# do.net
KiCad netlist of a schematic drawn in Altium Designer
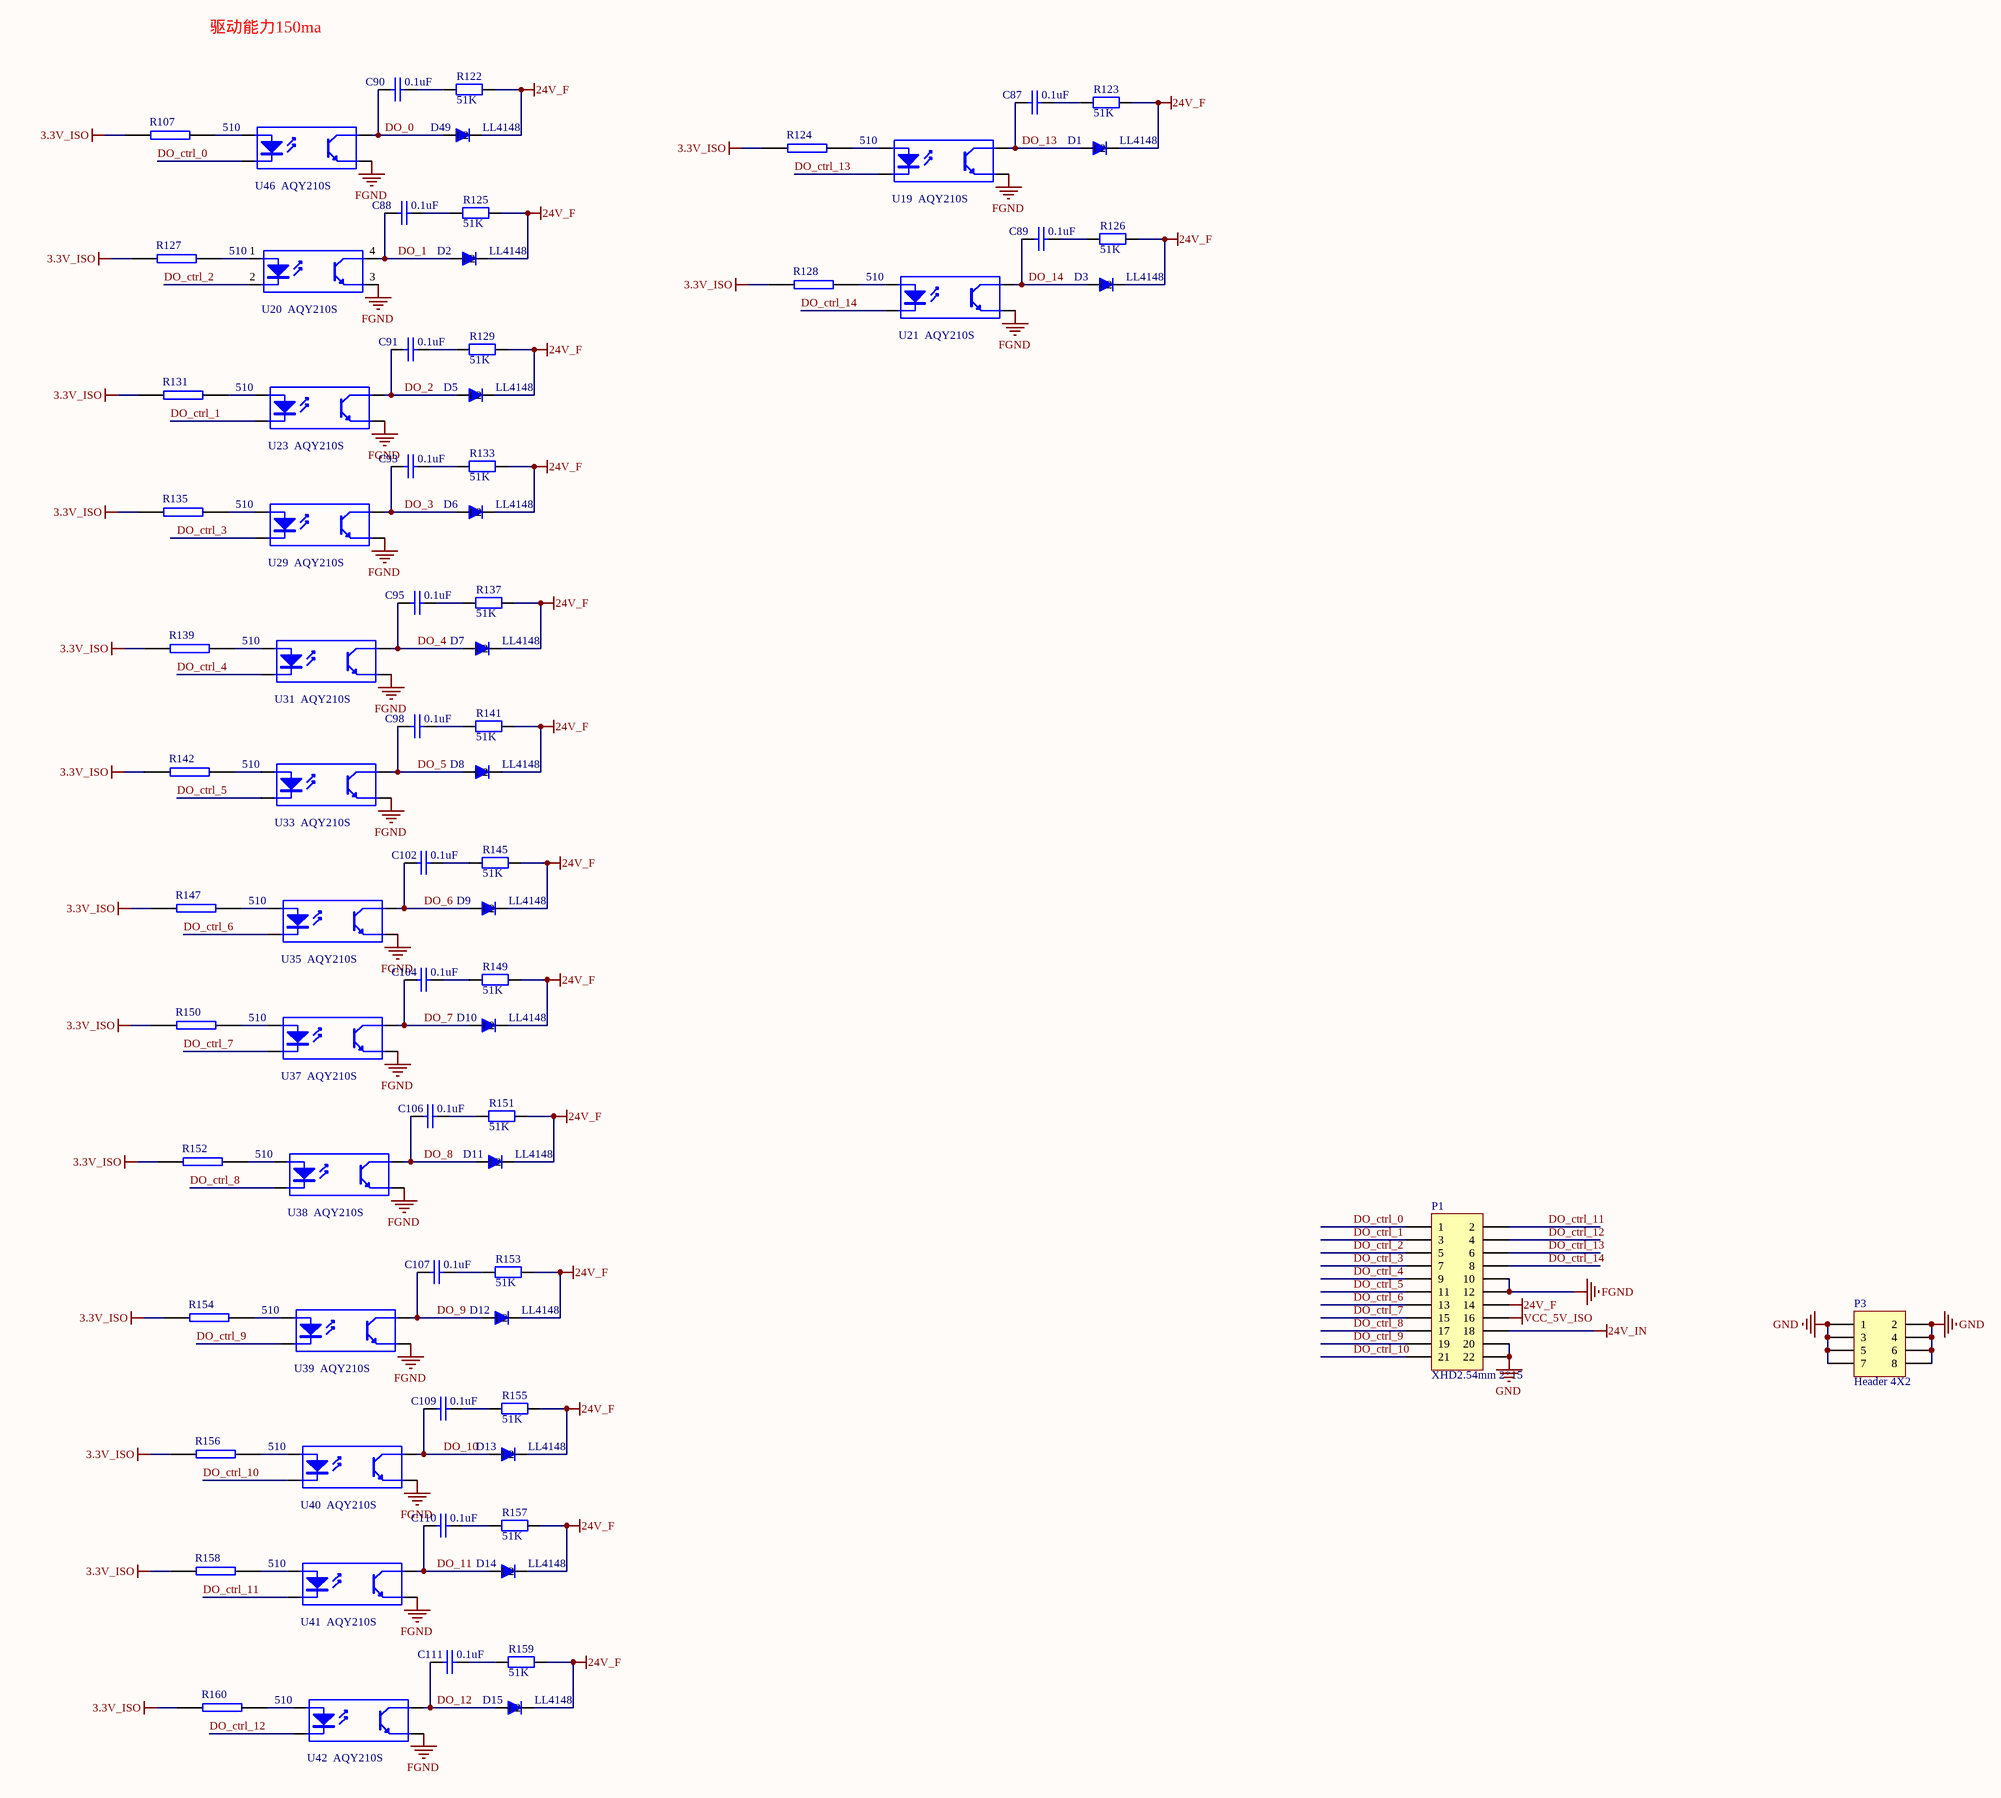
[diagram p0: do.SchDoc]

(export (version "E")
  (design (tool "Eeschema 10.0.6"))
  (components
    (comp (ref "C87")
      (value "0.1uF")
      (footprint "0603C")
      (description "Capacitor")
      (libsource (lib "*") (part "CAP"))
    )
    (comp (ref "C88")
      (value "0.1uF")
      (footprint "0603C")
      (description "Capacitor")
      (libsource (lib "*") (part "CAP"))
    )
    (comp (ref "C89")
      (value "0.1uF")
      (footprint "0603C")
      (description "Capacitor")
      (libsource (lib "*") (part "CAP"))
    )
    (comp (ref "C90")
      (value "0.1uF")
      (footprint "0603C")
      (description "Capacitor")
      (libsource (lib "*") (part "CAP"))
    )
    (comp (ref "C91")
      (value "0.1uF")
      (footprint "0603C")
      (description "Capacitor")
      (libsource (lib "*") (part "CAP"))
    )
    (comp (ref "C93")
      (value "0.1uF")
      (footprint "0603C")
      (description "Capacitor")
      (libsource (lib "*") (part "CAP"))
    )
    (comp (ref "C95")
      (value "0.1uF")
      (footprint "0603C")
      (description "Capacitor")
      (libsource (lib "*") (part "CAP"))
    )
    (comp (ref "C98")
      (value "0.1uF")
      (footprint "0603C")
      (description "Capacitor")
      (libsource (lib "*") (part "CAP"))
    )
    (comp (ref "C102")
      (value "0.1uF")
      (footprint "0603C")
      (description "Capacitor")
      (libsource (lib "*") (part "CAP"))
    )
    (comp (ref "C104")
      (value "0.1uF")
      (footprint "0603C")
      (description "Capacitor")
      (libsource (lib "*") (part "CAP"))
    )
    (comp (ref "C106")
      (value "0.1uF")
      (footprint "0603C")
      (description "Capacitor")
      (libsource (lib "*") (part "CAP"))
    )
    (comp (ref "C107")
      (value "0.1uF")
      (footprint "0603C")
      (description "Capacitor")
      (libsource (lib "*") (part "CAP"))
    )
    (comp (ref "C109")
      (value "0.1uF")
      (footprint "0603C")
      (description "Capacitor")
      (libsource (lib "*") (part "CAP"))
    )
    (comp (ref "C110")
      (value "0.1uF")
      (footprint "0603C")
      (description "Capacitor")
      (libsource (lib "*") (part "CAP"))
    )
    (comp (ref "C111")
      (value "0.1uF")
      (footprint "0603C")
      (description "Capacitor")
      (libsource (lib "*") (part "CAP"))
    )
    (comp (ref "D1")
      (value "LL4148")
      (footprint "DO-213AB/LL34/MiniMELF")
      (description "VISHAY,LL4148,圆柱体MiniMELF100V/2A,ROHS")
      (libsource (lib "Device2018") (part "LL4148"))
    )
    (comp (ref "D2")
      (value "LL4148")
      (footprint "DO-213AB/LL34/MiniMELF")
      (description "VISHAY,LL4148,圆柱体MiniMELF100V/2A,ROHS")
      (libsource (lib "Device2018") (part "LL4148"))
    )
    (comp (ref "D3")
      (value "LL4148")
      (footprint "DO-213AB/LL34/MiniMELF")
      (description "VISHAY,LL4148,圆柱体MiniMELF100V/2A,ROHS")
      (libsource (lib "Device2018") (part "LL4148"))
    )
    (comp (ref "D5")
      (value "LL4148")
      (footprint "DO-213AB/LL34/MiniMELF")
      (description "VISHAY,LL4148,圆柱体MiniMELF100V/2A,ROHS")
      (libsource (lib "Device2018") (part "LL4148"))
    )
    (comp (ref "D6")
      (value "LL4148")
      (footprint "DO-213AB/LL34/MiniMELF")
      (description "VISHAY,LL4148,圆柱体MiniMELF100V/2A,ROHS")
      (libsource (lib "Device2018") (part "LL4148"))
    )
    (comp (ref "D7")
      (value "LL4148")
      (footprint "DO-213AB/LL34/MiniMELF")
      (description "VISHAY,LL4148,圆柱体MiniMELF100V/2A,ROHS")
      (libsource (lib "Device2018") (part "LL4148"))
    )
    (comp (ref "D8")
      (value "LL4148")
      (footprint "DO-213AB/LL34/MiniMELF")
      (description "VISHAY,LL4148,圆柱体MiniMELF100V/2A,ROHS")
      (libsource (lib "Device2018") (part "LL4148"))
    )
    (comp (ref "D9")
      (value "LL4148")
      (footprint "DO-213AB/LL34/MiniMELF")
      (description "VISHAY,LL4148,圆柱体MiniMELF100V/2A,ROHS")
      (libsource (lib "Device2018") (part "LL4148"))
    )
    (comp (ref "D10")
      (value "LL4148")
      (footprint "DO-213AB/LL34/MiniMELF")
      (description "VISHAY,LL4148,圆柱体MiniMELF100V/2A,ROHS")
      (libsource (lib "Device2018") (part "LL4148"))
    )
    (comp (ref "D11")
      (value "LL4148")
      (footprint "DO-213AB/LL34/MiniMELF")
      (description "VISHAY,LL4148,圆柱体MiniMELF100V/2A,ROHS")
      (libsource (lib "Device2018") (part "LL4148"))
    )
    (comp (ref "D12")
      (value "LL4148")
      (footprint "DO-213AB/LL34/MiniMELF")
      (description "VISHAY,LL4148,圆柱体MiniMELF100V/2A,ROHS")
      (libsource (lib "Device2018") (part "LL4148"))
    )
    (comp (ref "D13")
      (value "LL4148")
      (footprint "DO-213AB/LL34/MiniMELF")
      (description "VISHAY,LL4148,圆柱体MiniMELF100V/2A,ROHS")
      (libsource (lib "Device2018") (part "LL4148"))
    )
    (comp (ref "D14")
      (value "LL4148")
      (footprint "DO-213AB/LL34/MiniMELF")
      (description "VISHAY,LL4148,圆柱体MiniMELF100V/2A,ROHS")
      (libsource (lib "Device2018") (part "LL4148"))
    )
    (comp (ref "D15")
      (value "LL4148")
      (footprint "DO-213AB/LL34/MiniMELF")
      (description "VISHAY,LL4148,圆柱体MiniMELF100V/2A,ROHS")
      (libsource (lib "Device2018") (part "LL4148"))
    )
    (comp (ref "D49")
      (value "LL4148")
      (footprint "DO-213AB/LL34/MiniMELF")
      (description "VISHAY,LL4148,圆柱体MiniMELF100V/2A,ROHS")
      (libsource (lib "Device2018") (part "LL4148"))
    )
    (comp (ref "P1")
      (value "XHD2.54mm 2*15")
      (footprint "HDR2X11")
      (description "Header, 11-Pin, Dual row")
      (fields (field (name "PUBLISHER") "Altium Limited"))
      (libsource (lib "Miscellaneous Connectors") (part "Header 11X2"))
    )
    (comp (ref "P3")
      (value "Header 4X2")
      (footprint "HDR2X4")
      (description "Header, 4-Pin, Dual row")
      (fields (field (name "PUBLISHER") "Altium Limited"))
      (libsource (lib "Miscellaneous Connectors") (part "Header 4X2"))
    )
    (comp (ref "R107") (value "510") (footprint "0603R") (libsource (lib "*") (part "RES2")))
    (comp (ref "R122") (value "51K") (footprint "0603R") (libsource (lib "MQlibrary") (part "Res0805M")))
    (comp (ref "R123") (value "51K") (footprint "0603R") (libsource (lib "MQlibrary") (part "Res0805M")))
    (comp (ref "R124") (value "510") (footprint "0603R") (libsource (lib "*") (part "RES2")))
    (comp (ref "R125") (value "51K") (footprint "0603R") (libsource (lib "MQlibrary") (part "Res0805M")))
    (comp (ref "R126") (value "51K") (footprint "0603R") (libsource (lib "MQlibrary") (part "Res0805M")))
    (comp (ref "R127") (value "510") (footprint "0603R") (libsource (lib "*") (part "RES2")))
    (comp (ref "R128") (value "510") (footprint "0603R") (libsource (lib "*") (part "RES2")))
    (comp (ref "R129") (value "51K") (footprint "0603R") (libsource (lib "MQlibrary") (part "Res0805M")))
    (comp (ref "R131") (value "510") (footprint "0603R") (libsource (lib "*") (part "RES2")))
    (comp (ref "R133") (value "51K") (footprint "0603R") (libsource (lib "MQlibrary") (part "Res0805M")))
    (comp (ref "R135") (value "510") (footprint "0603R") (libsource (lib "*") (part "RES2")))
    (comp (ref "R137") (value "51K") (footprint "0603R") (libsource (lib "MQlibrary") (part "Res0805M")))
    (comp (ref "R139") (value "510") (footprint "0603R") (libsource (lib "*") (part "RES2")))
    (comp (ref "R141") (value "51K") (footprint "0603R") (libsource (lib "MQlibrary") (part "Res0805M")))
    (comp (ref "R142") (value "510") (footprint "0603R") (libsource (lib "*") (part "RES2")))
    (comp (ref "R145") (value "51K") (footprint "0603R") (libsource (lib "MQlibrary") (part "Res0805M")))
    (comp (ref "R147") (value "510") (footprint "0603R") (libsource (lib "*") (part "RES2")))
    (comp (ref "R149") (value "51K") (footprint "0603R") (libsource (lib "MQlibrary") (part "Res0805M")))
    (comp (ref "R150") (value "510") (footprint "0603R") (libsource (lib "*") (part "RES2")))
    (comp (ref "R151") (value "51K") (footprint "0603R") (libsource (lib "MQlibrary") (part "Res0805M")))
    (comp (ref "R152") (value "510") (footprint "0603R") (libsource (lib "*") (part "RES2")))
    (comp (ref "R153") (value "51K") (footprint "0603R") (libsource (lib "MQlibrary") (part "Res0805M")))
    (comp (ref "R154") (value "510") (footprint "0603R") (libsource (lib "*") (part "RES2")))
    (comp (ref "R155") (value "51K") (footprint "0603R") (libsource (lib "MQlibrary") (part "Res0805M")))
    (comp (ref "R156") (value "510") (footprint "0603R") (libsource (lib "*") (part "RES2")))
    (comp (ref "R157") (value "51K") (footprint "0603R") (libsource (lib "MQlibrary") (part "Res0805M")))
    (comp (ref "R158") (value "510") (footprint "0603R") (libsource (lib "*") (part "RES2")))
    (comp (ref "R159") (value "51K") (footprint "0603R") (libsource (lib "MQlibrary") (part "Res0805M")))
    (comp (ref "R160") (value "510") (footprint "0603R") (libsource (lib "*") (part "RES2")))
    (comp (ref "U19")
      (value "AQY210S")
      (footprint "sop4")
      (description "4-Pin Phototransistor Optocoupler")
      (fields (field (name "PUBLISHER") "Altium Limited"))
      (libsource (lib "Miscellaneous Devices") (part "Optoisolator1"))
    )
    (comp (ref "U20")
      (value "AQY210S")
      (footprint "sop4")
      (description "4-Pin Phototransistor Optocoupler")
      (fields (field (name "PUBLISHER") "Altium Limited"))
      (libsource (lib "") (part "Optoisolator1_1"))
    )
    (comp (ref "U21")
      (value "AQY210S")
      (footprint "sop4")
      (description "4-Pin Phototransistor Optocoupler")
      (fields (field (name "PUBLISHER") "Altium Limited"))
      (libsource (lib "Miscellaneous Devices") (part "Optoisolator1"))
    )
    (comp (ref "U23")
      (value "AQY210S")
      (footprint "sop4")
      (description "4-Pin Phototransistor Optocoupler")
      (fields (field (name "PUBLISHER") "Altium Limited"))
      (libsource (lib "Miscellaneous Devices") (part "Optoisolator1"))
    )
    (comp (ref "U29")
      (value "AQY210S")
      (footprint "sop4")
      (description "4-Pin Phototransistor Optocoupler")
      (fields (field (name "PUBLISHER") "Altium Limited"))
      (libsource (lib "Miscellaneous Devices") (part "Optoisolator1"))
    )
    (comp (ref "U31")
      (value "AQY210S")
      (footprint "sop4")
      (description "4-Pin Phototransistor Optocoupler")
      (fields (field (name "PUBLISHER") "Altium Limited"))
      (libsource (lib "Miscellaneous Devices") (part "Optoisolator1"))
    )
    (comp (ref "U33")
      (value "AQY210S")
      (footprint "sop4")
      (description "4-Pin Phototransistor Optocoupler")
      (fields (field (name "PUBLISHER") "Altium Limited"))
      (libsource (lib "Miscellaneous Devices") (part "Optoisolator1"))
    )
    (comp (ref "U35")
      (value "AQY210S")
      (footprint "sop4")
      (description "4-Pin Phototransistor Optocoupler")
      (fields (field (name "PUBLISHER") "Altium Limited"))
      (libsource (lib "Miscellaneous Devices") (part "Optoisolator1"))
    )
    (comp (ref "U37")
      (value "AQY210S")
      (footprint "sop4")
      (description "4-Pin Phototransistor Optocoupler")
      (fields (field (name "PUBLISHER") "Altium Limited"))
      (libsource (lib "Miscellaneous Devices") (part "Optoisolator1"))
    )
    (comp (ref "U38")
      (value "AQY210S")
      (footprint "sop4")
      (description "4-Pin Phototransistor Optocoupler")
      (fields (field (name "PUBLISHER") "Altium Limited"))
      (libsource (lib "Miscellaneous Devices") (part "Optoisolator1"))
    )
    (comp (ref "U39")
      (value "AQY210S")
      (footprint "sop4")
      (description "4-Pin Phototransistor Optocoupler")
      (fields (field (name "PUBLISHER") "Altium Limited"))
      (libsource (lib "Miscellaneous Devices") (part "Optoisolator1"))
    )
    (comp (ref "U40")
      (value "AQY210S")
      (footprint "sop4")
      (description "4-Pin Phototransistor Optocoupler")
      (fields (field (name "PUBLISHER") "Altium Limited"))
      (libsource (lib "Miscellaneous Devices") (part "Optoisolator1"))
    )
    (comp (ref "U41")
      (value "AQY210S")
      (footprint "sop4")
      (description "4-Pin Phototransistor Optocoupler")
      (fields (field (name "PUBLISHER") "Altium Limited"))
      (libsource (lib "Miscellaneous Devices") (part "Optoisolator1"))
    )
    (comp (ref "U42")
      (value "AQY210S")
      (footprint "sop4")
      (description "4-Pin Phototransistor Optocoupler")
      (fields (field (name "PUBLISHER") "Altium Limited"))
      (libsource (lib "Miscellaneous Devices") (part "Optoisolator1"))
    )
    (comp (ref "U46")
      (value "AQY210S")
      (footprint "sop4")
      (description "4-Pin Phototransistor Optocoupler")
      (fields (field (name "PUBLISHER") "Altium Limited"))
      (libsource (lib "Miscellaneous Devices") (part "Optoisolator1"))
    )
  )
  (nets
    (net (code "1") (name "/DO_0") (class "Default")
      (node (ref "C90") (pin "1") (pinfunction "1_1") (pintype "passive"))
      (node (ref "D49") (pin "1") (pinfunction "2_1") (pintype "passive"))
      (node (ref "U46") (pin "4") (pinfunction "C_4") (pintype "passive"))
    )
    (net (code "2") (name "/DO_1") (class "Default")
      (node (ref "C88") (pin "1") (pinfunction "1_1") (pintype "passive"))
      (node (ref "D2") (pin "1") (pinfunction "2_1") (pintype "passive"))
      (node (ref "U20") (pin "4") (pinfunction "C_4") (pintype "passive"))
    )
    (net (code "3") (name "/DO_2") (class "Default")
      (node (ref "C91") (pin "1") (pinfunction "1_1") (pintype "passive"))
      (node (ref "D5") (pin "1") (pinfunction "2_1") (pintype "passive"))
      (node (ref "U23") (pin "4") (pinfunction "C_4") (pintype "passive"))
    )
    (net (code "4") (name "/DO_3") (class "Default")
      (node (ref "C93") (pin "1") (pinfunction "1_1") (pintype "passive"))
      (node (ref "D6") (pin "1") (pinfunction "2_1") (pintype "passive"))
      (node (ref "U29") (pin "4") (pinfunction "C_4") (pintype "passive"))
    )
    (net (code "5") (name "/DO_4") (class "Default")
      (node (ref "C95") (pin "1") (pinfunction "1_1") (pintype "passive"))
      (node (ref "D7") (pin "1") (pinfunction "2_1") (pintype "passive"))
      (node (ref "U31") (pin "4") (pinfunction "C_4") (pintype "passive"))
    )
    (net (code "6") (name "/DO_5") (class "Default")
      (node (ref "C98") (pin "1") (pinfunction "1_1") (pintype "passive"))
      (node (ref "D8") (pin "1") (pinfunction "2_1") (pintype "passive"))
      (node (ref "U33") (pin "4") (pinfunction "C_4") (pintype "passive"))
    )
    (net (code "7") (name "/DO_6") (class "Default")
      (node (ref "C102") (pin "1") (pinfunction "1_1") (pintype "passive"))
      (node (ref "D9") (pin "1") (pinfunction "2_1") (pintype "passive"))
      (node (ref "U35") (pin "4") (pinfunction "C_4") (pintype "passive"))
    )
    (net (code "8") (name "/DO_7") (class "Default")
      (node (ref "C104") (pin "1") (pinfunction "1_1") (pintype "passive"))
      (node (ref "D10") (pin "1") (pinfunction "2_1") (pintype "passive"))
      (node (ref "U37") (pin "4") (pinfunction "C_4") (pintype "passive"))
    )
    (net (code "9") (name "/DO_8") (class "Default")
      (node (ref "C106") (pin "1") (pinfunction "1_1") (pintype "passive"))
      (node (ref "D11") (pin "1") (pinfunction "2_1") (pintype "passive"))
      (node (ref "U38") (pin "4") (pinfunction "C_4") (pintype "passive"))
    )
    (net (code "10") (name "/DO_9") (class "Default")
      (node (ref "C107") (pin "1") (pinfunction "1_1") (pintype "passive"))
      (node (ref "D12") (pin "1") (pinfunction "2_1") (pintype "passive"))
      (node (ref "U39") (pin "4") (pinfunction "C_4") (pintype "passive"))
    )
    (net (code "11") (name "/DO_10") (class "Default")
      (node (ref "C109") (pin "1") (pinfunction "1_1") (pintype "passive"))
      (node (ref "D13") (pin "1") (pinfunction "2_1") (pintype "passive"))
      (node (ref "U40") (pin "4") (pinfunction "C_4") (pintype "passive"))
    )
    (net (code "12") (name "/DO_11") (class "Default")
      (node (ref "C110") (pin "1") (pinfunction "1_1") (pintype "passive"))
      (node (ref "D14") (pin "1") (pinfunction "2_1") (pintype "passive"))
      (node (ref "U41") (pin "4") (pinfunction "C_4") (pintype "passive"))
    )
    (net (code "13") (name "/DO_12") (class "Default")
      (node (ref "C111") (pin "1") (pinfunction "1_1") (pintype "passive"))
      (node (ref "D15") (pin "1") (pinfunction "2_1") (pintype "passive"))
      (node (ref "U42") (pin "4") (pinfunction "C_4") (pintype "passive"))
    )
    (net (code "14") (name "/DO_13") (class "Default")
      (node (ref "C87") (pin "1") (pinfunction "1_1") (pintype "passive"))
      (node (ref "D1") (pin "1") (pinfunction "2_1") (pintype "passive"))
      (node (ref "U19") (pin "4") (pinfunction "C_4") (pintype "passive"))
    )
    (net (code "15") (name "/DO_14") (class "Default")
      (node (ref "C89") (pin "1") (pinfunction "1_1") (pintype "passive"))
      (node (ref "D3") (pin "1") (pinfunction "2_1") (pintype "passive"))
      (node (ref "U21") (pin "4") (pinfunction "C_4") (pintype "passive"))
    )
    (net (code "16") (name "/DO_ctrl_0") (class "Default")
      (node (ref "P1") (pin "1") (pinfunction "1_1") (pintype "passive"))
      (node (ref "U46") (pin "2") (pinfunction "K_2") (pintype "passive"))
    )
    (net (code "17") (name "/DO_ctrl_1") (class "Default")
      (node (ref "P1") (pin "3") (pinfunction "3_3") (pintype "passive"))
      (node (ref "U23") (pin "2") (pinfunction "K_2") (pintype "passive"))
    )
    (net (code "18") (name "/DO_ctrl_2") (class "Default")
      (node (ref "P1") (pin "5") (pinfunction "5_5") (pintype "passive"))
      (node (ref "U20") (pin "2") (pinfunction "K_2") (pintype "passive"))
    )
    (net (code "19") (name "/DO_ctrl_3") (class "Default")
      (node (ref "P1") (pin "7") (pinfunction "7_7") (pintype "passive"))
      (node (ref "U29") (pin "2") (pinfunction "K_2") (pintype "passive"))
    )
    (net (code "20") (name "/DO_ctrl_4") (class "Default")
      (node (ref "P1") (pin "9") (pinfunction "9_9") (pintype "passive"))
      (node (ref "U31") (pin "2") (pinfunction "K_2") (pintype "passive"))
    )
    (net (code "21") (name "/DO_ctrl_5") (class "Default")
      (node (ref "P1") (pin "11") (pinfunction "11_11") (pintype "passive"))
      (node (ref "U33") (pin "2") (pinfunction "K_2") (pintype "passive"))
    )
    (net (code "22") (name "/DO_ctrl_6") (class "Default")
      (node (ref "P1") (pin "13") (pinfunction "13_13") (pintype "passive"))
      (node (ref "U35") (pin "2") (pinfunction "K_2") (pintype "passive"))
    )
    (net (code "23") (name "/DO_ctrl_7") (class "Default")
      (node (ref "P1") (pin "15") (pinfunction "15_15") (pintype "passive"))
      (node (ref "U37") (pin "2") (pinfunction "K_2") (pintype "passive"))
    )
    (net (code "24") (name "/DO_ctrl_8") (class "Default")
      (node (ref "P1") (pin "17") (pinfunction "17_17") (pintype "passive"))
      (node (ref "U38") (pin "2") (pinfunction "K_2") (pintype "passive"))
    )
    (net (code "25") (name "/DO_ctrl_9") (class "Default")
      (node (ref "P1") (pin "19") (pinfunction "19_19") (pintype "passive"))
      (node (ref "U39") (pin "2") (pinfunction "K_2") (pintype "passive"))
    )
    (net (code "26") (name "/DO_ctrl_10") (class "Default")
      (node (ref "P1") (pin "21") (pinfunction "21_21") (pintype "passive"))
      (node (ref "U40") (pin "2") (pinfunction "K_2") (pintype "passive"))
    )
    (net (code "27") (name "/DO_ctrl_11") (class "Default")
      (node (ref "P1") (pin "2") (pinfunction "2_2") (pintype "passive"))
      (node (ref "U41") (pin "2") (pinfunction "K_2") (pintype "passive"))
    )
    (net (code "28") (name "/DO_ctrl_12") (class "Default")
      (node (ref "P1") (pin "4") (pinfunction "4_4") (pintype "passive"))
      (node (ref "U42") (pin "2") (pinfunction "K_2") (pintype "passive"))
    )
    (net (code "29") (name "/DO_ctrl_13") (class "Default")
      (node (ref "P1") (pin "6") (pinfunction "6_6") (pintype "passive"))
      (node (ref "U19") (pin "2") (pinfunction "K_2") (pintype "passive"))
    )
    (net (code "30") (name "/DO_ctrl_14") (class "Default")
      (node (ref "P1") (pin "8") (pinfunction "8_8") (pintype "passive"))
      (node (ref "U21") (pin "2") (pinfunction "K_2") (pintype "passive"))
    )
    (net (code "31") (name "3.3V_ISO") (class "Default")
      (node (ref "R107") (pin "2") (pinfunction "2_2") (pintype "passive"))
      (node (ref "R124") (pin "2") (pinfunction "2_2") (pintype "passive"))
      (node (ref "R127") (pin "2") (pinfunction "2_2") (pintype "passive"))
      (node (ref "R128") (pin "2") (pinfunction "2_2") (pintype "passive"))
      (node (ref "R131") (pin "2") (pinfunction "2_2") (pintype "passive"))
      (node (ref "R135") (pin "2") (pinfunction "2_2") (pintype "passive"))
      (node (ref "R139") (pin "2") (pinfunction "2_2") (pintype "passive"))
      (node (ref "R142") (pin "2") (pinfunction "2_2") (pintype "passive"))
      (node (ref "R147") (pin "2") (pinfunction "2_2") (pintype "passive"))
      (node (ref "R150") (pin "2") (pinfunction "2_2") (pintype "passive"))
      (node (ref "R152") (pin "2") (pinfunction "2_2") (pintype "passive"))
      (node (ref "R154") (pin "2") (pinfunction "2_2") (pintype "passive"))
      (node (ref "R156") (pin "2") (pinfunction "2_2") (pintype "passive"))
      (node (ref "R158") (pin "2") (pinfunction "2_2") (pintype "passive"))
      (node (ref "R160") (pin "2") (pinfunction "2_2") (pintype "passive"))
    )
    (net (code "32") (name "24V_F") (class "Default")
      (node (ref "D1") (pin "2") (pinfunction "1_2") (pintype "passive"))
      (node (ref "D10") (pin "2") (pinfunction "1_2") (pintype "passive"))
      (node (ref "D11") (pin "2") (pinfunction "1_2") (pintype "passive"))
      (node (ref "D12") (pin "2") (pinfunction "1_2") (pintype "passive"))
      (node (ref "D13") (pin "2") (pinfunction "1_2") (pintype "passive"))
      (node (ref "D14") (pin "2") (pinfunction "1_2") (pintype "passive"))
      (node (ref "D15") (pin "2") (pinfunction "1_2") (pintype "passive"))
      (node (ref "D2") (pin "2") (pinfunction "1_2") (pintype "passive"))
      (node (ref "D3") (pin "2") (pinfunction "1_2") (pintype "passive"))
      (node (ref "D49") (pin "2") (pinfunction "1_2") (pintype "passive"))
      (node (ref "D5") (pin "2") (pinfunction "1_2") (pintype "passive"))
      (node (ref "D6") (pin "2") (pinfunction "1_2") (pintype "passive"))
      (node (ref "D7") (pin "2") (pinfunction "1_2") (pintype "passive"))
      (node (ref "D8") (pin "2") (pinfunction "1_2") (pintype "passive"))
      (node (ref "D9") (pin "2") (pinfunction "1_2") (pintype "passive"))
      (node (ref "P1") (pin "14") (pinfunction "14_14") (pintype "passive"))
      (node (ref "R122") (pin "2") (pinfunction "2_2") (pintype "passive"))
      (node (ref "R123") (pin "2") (pinfunction "2_2") (pintype "passive"))
      (node (ref "R125") (pin "2") (pinfunction "2_2") (pintype "passive"))
      (node (ref "R126") (pin "2") (pinfunction "2_2") (pintype "passive"))
      (node (ref "R129") (pin "2") (pinfunction "2_2") (pintype "passive"))
      (node (ref "R133") (pin "2") (pinfunction "2_2") (pintype "passive"))
      (node (ref "R137") (pin "2") (pinfunction "2_2") (pintype "passive"))
      (node (ref "R141") (pin "2") (pinfunction "2_2") (pintype "passive"))
      (node (ref "R145") (pin "2") (pinfunction "2_2") (pintype "passive"))
      (node (ref "R149") (pin "2") (pinfunction "2_2") (pintype "passive"))
      (node (ref "R151") (pin "2") (pinfunction "2_2") (pintype "passive"))
      (node (ref "R153") (pin "2") (pinfunction "2_2") (pintype "passive"))
      (node (ref "R155") (pin "2") (pinfunction "2_2") (pintype "passive"))
      (node (ref "R157") (pin "2") (pinfunction "2_2") (pintype "passive"))
      (node (ref "R159") (pin "2") (pinfunction "2_2") (pintype "passive"))
    )
    (net (code "33") (name "24V_IN") (class "Default")
      (node (ref "P1") (pin "18") (pinfunction "18_18") (pintype "passive"))
    )
    (net (code "34") (name "FGND") (class "Default")
      (node (ref "P1") (pin "10") (pinfunction "10_10") (pintype "passive"))
      (node (ref "P1") (pin "12") (pinfunction "12_12") (pintype "passive"))
      (node (ref "U19") (pin "3") (pinfunction "E_3") (pintype "passive"))
      (node (ref "U20") (pin "3") (pinfunction "E_3") (pintype "passive"))
      (node (ref "U21") (pin "3") (pinfunction "E_3") (pintype "passive"))
      (node (ref "U23") (pin "3") (pinfunction "E_3") (pintype "passive"))
      (node (ref "U29") (pin "3") (pinfunction "E_3") (pintype "passive"))
      (node (ref "U31") (pin "3") (pinfunction "E_3") (pintype "passive"))
      (node (ref "U33") (pin "3") (pinfunction "E_3") (pintype "passive"))
      (node (ref "U35") (pin "3") (pinfunction "E_3") (pintype "passive"))
      (node (ref "U37") (pin "3") (pinfunction "E_3") (pintype "passive"))
      (node (ref "U38") (pin "3") (pinfunction "E_3") (pintype "passive"))
      (node (ref "U39") (pin "3") (pinfunction "E_3") (pintype "passive"))
      (node (ref "U40") (pin "3") (pinfunction "E_3") (pintype "passive"))
      (node (ref "U41") (pin "3") (pinfunction "E_3") (pintype "passive"))
      (node (ref "U42") (pin "3") (pinfunction "E_3") (pintype "passive"))
      (node (ref "U46") (pin "3") (pinfunction "E_3") (pintype "passive"))
    )
    (net (code "35") (name "GND") (class "Default")
      (node (ref "P1") (pin "20") (pinfunction "20_20") (pintype "passive"))
      (node (ref "P1") (pin "22") (pinfunction "22_22") (pintype "passive"))
      (node (ref "P3") (pin "1") (pinfunction "1_1") (pintype "passive"))
      (node (ref "P3") (pin "2") (pinfunction "2_2") (pintype "passive"))
      (node (ref "P3") (pin "3") (pinfunction "3_3") (pintype "passive"))
      (node (ref "P3") (pin "4") (pinfunction "4_4") (pintype "passive"))
      (node (ref "P3") (pin "5") (pinfunction "5_5") (pintype "passive"))
      (node (ref "P3") (pin "6") (pinfunction "6_6") (pintype "passive"))
      (node (ref "P3") (pin "7") (pinfunction "7_7") (pintype "passive"))
      (node (ref "P3") (pin "8") (pinfunction "8_8") (pintype "passive"))
    )
    (net (code "36") (name "Net-(C87-Pad2)") (class "Default")
      (node (ref "C87") (pin "2") (pinfunction "2_2") (pintype "passive"))
      (node (ref "R123") (pin "1") (pinfunction "1_1") (pintype "passive"))
    )
    (net (code "37") (name "Net-(C88-Pad2)") (class "Default")
      (node (ref "C88") (pin "2") (pinfunction "2_2") (pintype "passive"))
      (node (ref "R125") (pin "1") (pinfunction "1_1") (pintype "passive"))
    )
    (net (code "38") (name "Net-(C89-Pad2)") (class "Default")
      (node (ref "C89") (pin "2") (pinfunction "2_2") (pintype "passive"))
      (node (ref "R126") (pin "1") (pinfunction "1_1") (pintype "passive"))
    )
    (net (code "39") (name "Net-(C90-Pad2)") (class "Default")
      (node (ref "C90") (pin "2") (pinfunction "2_2") (pintype "passive"))
      (node (ref "R122") (pin "1") (pinfunction "1_1") (pintype "passive"))
    )
    (net (code "40") (name "Net-(C91-Pad2)") (class "Default")
      (node (ref "C91") (pin "2") (pinfunction "2_2") (pintype "passive"))
      (node (ref "R129") (pin "1") (pinfunction "1_1") (pintype "passive"))
    )
    (net (code "41") (name "Net-(C93-Pad2)") (class "Default")
      (node (ref "C93") (pin "2") (pinfunction "2_2") (pintype "passive"))
      (node (ref "R133") (pin "1") (pinfunction "1_1") (pintype "passive"))
    )
    (net (code "42") (name "Net-(C95-Pad2)") (class "Default")
      (node (ref "C95") (pin "2") (pinfunction "2_2") (pintype "passive"))
      (node (ref "R137") (pin "1") (pinfunction "1_1") (pintype "passive"))
    )
    (net (code "43") (name "Net-(C98-Pad2)") (class "Default")
      (node (ref "C98") (pin "2") (pinfunction "2_2") (pintype "passive"))
      (node (ref "R141") (pin "1") (pinfunction "1_1") (pintype "passive"))
    )
    (net (code "44") (name "Net-(C102-Pad2)") (class "Default")
      (node (ref "C102") (pin "2") (pinfunction "2_2") (pintype "passive"))
      (node (ref "R145") (pin "1") (pinfunction "1_1") (pintype "passive"))
    )
    (net (code "45") (name "Net-(C104-Pad2)") (class "Default")
      (node (ref "C104") (pin "2") (pinfunction "2_2") (pintype "passive"))
      (node (ref "R149") (pin "1") (pinfunction "1_1") (pintype "passive"))
    )
    (net (code "46") (name "Net-(C106-Pad2)") (class "Default")
      (node (ref "C106") (pin "2") (pinfunction "2_2") (pintype "passive"))
      (node (ref "R151") (pin "1") (pinfunction "1_1") (pintype "passive"))
    )
    (net (code "47") (name "Net-(C107-Pad2)") (class "Default")
      (node (ref "C107") (pin "2") (pinfunction "2_2") (pintype "passive"))
      (node (ref "R153") (pin "1") (pinfunction "1_1") (pintype "passive"))
    )
    (net (code "48") (name "Net-(C109-Pad2)") (class "Default")
      (node (ref "C109") (pin "2") (pinfunction "2_2") (pintype "passive"))
      (node (ref "R155") (pin "1") (pinfunction "1_1") (pintype "passive"))
    )
    (net (code "49") (name "Net-(C110-Pad2)") (class "Default")
      (node (ref "C110") (pin "2") (pinfunction "2_2") (pintype "passive"))
      (node (ref "R157") (pin "1") (pinfunction "1_1") (pintype "passive"))
    )
    (net (code "50") (name "Net-(C111-Pad2)") (class "Default")
      (node (ref "C111") (pin "2") (pinfunction "2_2") (pintype "passive"))
      (node (ref "R159") (pin "1") (pinfunction "1_1") (pintype "passive"))
    )
    (net (code "51") (name "Net-(U19-A)") (class "Default")
      (node (ref "R124") (pin "1") (pinfunction "1_1") (pintype "passive"))
      (node (ref "U19") (pin "1") (pinfunction "A_1") (pintype "passive"))
    )
    (net (code "52") (name "Net-(U20-A)") (class "Default")
      (node (ref "R127") (pin "1") (pinfunction "1_1") (pintype "passive"))
      (node (ref "U20") (pin "1") (pinfunction "A_1") (pintype "passive"))
    )
    (net (code "53") (name "Net-(U21-A)") (class "Default")
      (node (ref "R128") (pin "1") (pinfunction "1_1") (pintype "passive"))
      (node (ref "U21") (pin "1") (pinfunction "A_1") (pintype "passive"))
    )
    (net (code "54") (name "Net-(U23-A)") (class "Default")
      (node (ref "R131") (pin "1") (pinfunction "1_1") (pintype "passive"))
      (node (ref "U23") (pin "1") (pinfunction "A_1") (pintype "passive"))
    )
    (net (code "55") (name "Net-(U29-A)") (class "Default")
      (node (ref "R135") (pin "1") (pinfunction "1_1") (pintype "passive"))
      (node (ref "U29") (pin "1") (pinfunction "A_1") (pintype "passive"))
    )
    (net (code "56") (name "Net-(U31-A)") (class "Default")
      (node (ref "R139") (pin "1") (pinfunction "1_1") (pintype "passive"))
      (node (ref "U31") (pin "1") (pinfunction "A_1") (pintype "passive"))
    )
    (net (code "57") (name "Net-(U33-A)") (class "Default")
      (node (ref "R142") (pin "1") (pinfunction "1_1") (pintype "passive"))
      (node (ref "U33") (pin "1") (pinfunction "A_1") (pintype "passive"))
    )
    (net (code "58") (name "Net-(U35-A)") (class "Default")
      (node (ref "R147") (pin "1") (pinfunction "1_1") (pintype "passive"))
      (node (ref "U35") (pin "1") (pinfunction "A_1") (pintype "passive"))
    )
    (net (code "59") (name "Net-(U37-A)") (class "Default")
      (node (ref "R150") (pin "1") (pinfunction "1_1") (pintype "passive"))
      (node (ref "U37") (pin "1") (pinfunction "A_1") (pintype "passive"))
    )
    (net (code "60") (name "Net-(U38-A)") (class "Default")
      (node (ref "R152") (pin "1") (pinfunction "1_1") (pintype "passive"))
      (node (ref "U38") (pin "1") (pinfunction "A_1") (pintype "passive"))
    )
    (net (code "61") (name "Net-(U39-A)") (class "Default")
      (node (ref "R154") (pin "1") (pinfunction "1_1") (pintype "passive"))
      (node (ref "U39") (pin "1") (pinfunction "A_1") (pintype "passive"))
    )
    (net (code "62") (name "Net-(U40-A)") (class "Default")
      (node (ref "R156") (pin "1") (pinfunction "1_1") (pintype "passive"))
      (node (ref "U40") (pin "1") (pinfunction "A_1") (pintype "passive"))
    )
    (net (code "63") (name "Net-(U41-A)") (class "Default")
      (node (ref "R158") (pin "1") (pinfunction "1_1") (pintype "passive"))
      (node (ref "U41") (pin "1") (pinfunction "A_1") (pintype "passive"))
    )
    (net (code "64") (name "Net-(U42-A)") (class "Default")
      (node (ref "R160") (pin "1") (pinfunction "1_1") (pintype "passive"))
      (node (ref "U42") (pin "1") (pinfunction "A_1") (pintype "passive"))
    )
    (net (code "65") (name "Net-(U46-A)") (class "Default")
      (node (ref "R107") (pin "1") (pinfunction "1_1") (pintype "passive"))
      (node (ref "U46") (pin "1") (pinfunction "A_1") (pintype "passive"))
    )
    (net (code "66") (name "VCC_5V_ISO") (class "Default")
      (node (ref "P1") (pin "16") (pinfunction "16_16") (pintype "passive"))
    )
  )
)
